# 19_RAM_Memory_module.net
KiCad netlist of a schematic drawn in Altium Designer
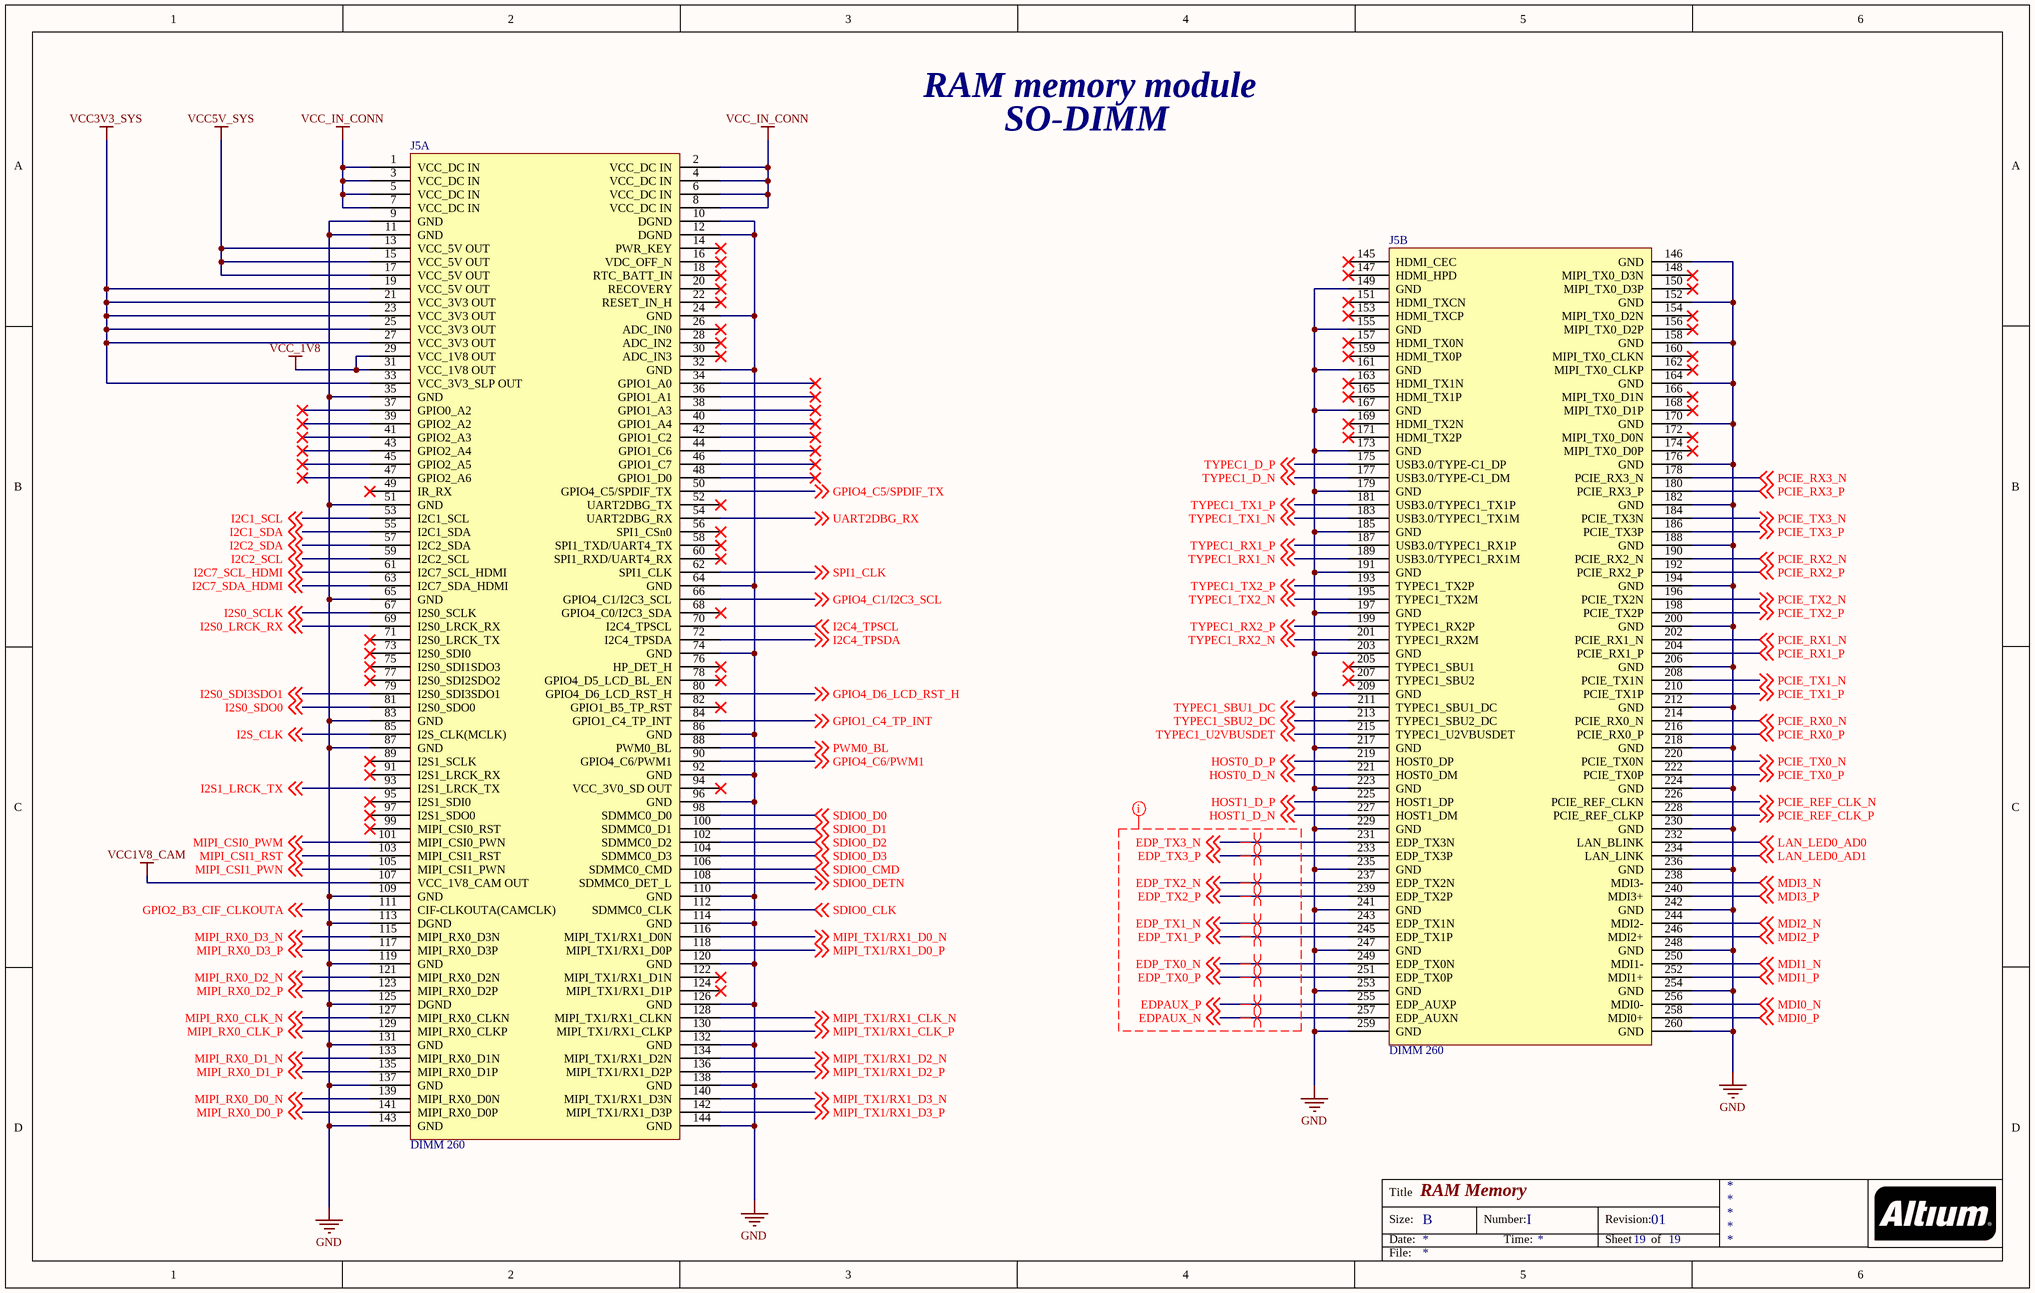
[diagram p0: [19] RAM Memory module.SchDoc]

(export (version "E")
  (design (tool "Eeschema 10.0.6"))
  (components
    (comp (ref "J5")
      (value "DIMM 260")
      (footprint "DIMM260_DDR4")
      (description "Dimm 260 pin smd plating on pcb")
      (fields (field (name "MANUFACTURER") "NA"))
      (libsource (lib "EsteemPCB_SOM_Course_intlib") (part "CON-DIMM_260-SMD"))
    )
  )
  (nets
    (net (code "1") (name "EDPAUX_N") (class "Default")
      (node (ref "J5") (pin "257") (pinfunction "EDP_AUXN_257") (pintype "passive"))
    )
    (net (code "2") (name "EDPAUX_P") (class "Default")
      (node (ref "J5") (pin "255") (pinfunction "EDP_AUXP_255") (pintype "passive"))
    )
    (net (code "3") (name "EDP_TX0_N") (class "Default")
      (node (ref "J5") (pin "249") (pinfunction "EDP_TX0N_249") (pintype "passive"))
    )
    (net (code "4") (name "EDP_TX0_P") (class "Default")
      (node (ref "J5") (pin "251") (pinfunction "EDP_TX0P_251") (pintype "passive"))
    )
    (net (code "5") (name "EDP_TX1_N") (class "Default")
      (node (ref "J5") (pin "243") (pinfunction "EDP_TX1N_243") (pintype "passive"))
    )
    (net (code "6") (name "EDP_TX1_P") (class "Default")
      (node (ref "J5") (pin "245") (pinfunction "EDP_TX1P_245") (pintype "passive"))
    )
    (net (code "7") (name "EDP_TX2_N") (class "Default")
      (node (ref "J5") (pin "237") (pinfunction "EDP_TX2N_237") (pintype "passive"))
    )
    (net (code "8") (name "EDP_TX2_P") (class "Default")
      (node (ref "J5") (pin "239") (pinfunction "EDP_TX2P_239") (pintype "passive"))
    )
    (net (code "9") (name "EDP_TX3_N") (class "Default")
      (node (ref "J5") (pin "231") (pinfunction "EDP_TX3N_231") (pintype "passive"))
    )
    (net (code "10") (name "EDP_TX3_P") (class "Default")
      (node (ref "J5") (pin "233") (pinfunction "EDP_TX3P_233") (pintype "passive"))
    )
    (net (code "11") (name "GND") (class "Default")
      (node (ref "J5") (pin "10") (pinfunction "DGND_10") (pintype "passive"))
      (node (ref "J5") (pin "109") (pinfunction "GND_109") (pintype "passive"))
      (node (ref "J5") (pin "11") (pinfunction "GND_11") (pintype "passive"))
      (node (ref "J5") (pin "110") (pinfunction "GND_110") (pintype "passive"))
      (node (ref "J5") (pin "113") (pinfunction "DGND_113") (pintype "passive"))
      (node (ref "J5") (pin "114") (pinfunction "GND_114") (pintype "passive"))
      (node (ref "J5") (pin "119") (pinfunction "GND_119") (pintype "passive"))
      (node (ref "J5") (pin "12") (pinfunction "DGND_12") (pintype "passive"))
      (node (ref "J5") (pin "120") (pinfunction "GND_120") (pintype "passive"))
      (node (ref "J5") (pin "125") (pinfunction "DGND_125") (pintype "passive"))
      (node (ref "J5") (pin "126") (pinfunction "GND_126") (pintype "passive"))
      (node (ref "J5") (pin "131") (pinfunction "GND_131") (pintype "passive"))
      (node (ref "J5") (pin "132") (pinfunction "GND_132") (pintype "passive"))
      (node (ref "J5") (pin "137") (pinfunction "GND_137") (pintype "passive"))
      (node (ref "J5") (pin "138") (pinfunction "GND_138") (pintype "passive"))
      (node (ref "J5") (pin "143") (pinfunction "GND_143") (pintype "passive"))
      (node (ref "J5") (pin "144") (pinfunction "GND_144") (pintype "passive"))
      (node (ref "J5") (pin "146") (pinfunction "GND_146") (pintype "passive"))
      (node (ref "J5") (pin "149") (pinfunction "GND_149") (pintype "passive"))
      (node (ref "J5") (pin "152") (pinfunction "GND_152") (pintype "passive"))
      (node (ref "J5") (pin "155") (pinfunction "GND_155") (pintype "passive"))
      (node (ref "J5") (pin "158") (pinfunction "GND_158") (pintype "passive"))
      (node (ref "J5") (pin "161") (pinfunction "GND_161") (pintype "passive"))
      (node (ref "J5") (pin "164") (pinfunction "GND_164") (pintype "passive"))
      (node (ref "J5") (pin "167") (pinfunction "GND_167") (pintype "passive"))
      (node (ref "J5") (pin "170") (pinfunction "GND_170") (pintype "passive"))
      (node (ref "J5") (pin "173") (pinfunction "GND_173") (pintype "passive"))
      (node (ref "J5") (pin "176") (pinfunction "GND_176") (pintype "passive"))
      (node (ref "J5") (pin "179") (pinfunction "GND_179") (pintype "passive"))
      (node (ref "J5") (pin "182") (pinfunction "GND_182") (pintype "passive"))
      (node (ref "J5") (pin "185") (pinfunction "GND_185") (pintype "passive"))
      (node (ref "J5") (pin "188") (pinfunction "GND_188") (pintype "passive"))
      (node (ref "J5") (pin "191") (pinfunction "GND_191") (pintype "passive"))
      (node (ref "J5") (pin "194") (pinfunction "GND_194") (pintype "passive"))
      (node (ref "J5") (pin "197") (pinfunction "GND_197") (pintype "passive"))
      (node (ref "J5") (pin "200") (pinfunction "GND_200") (pintype "passive"))
      (node (ref "J5") (pin "203") (pinfunction "GND_203") (pintype "passive"))
      (node (ref "J5") (pin "206") (pinfunction "GND_206") (pintype "passive"))
      (node (ref "J5") (pin "209") (pinfunction "GND_209") (pintype "passive"))
      (node (ref "J5") (pin "212") (pinfunction "GND_212") (pintype "passive"))
      (node (ref "J5") (pin "217") (pinfunction "GND_217") (pintype "passive"))
      (node (ref "J5") (pin "218") (pinfunction "GND_218") (pintype "passive"))
      (node (ref "J5") (pin "223") (pinfunction "GND_223") (pintype "passive"))
      (node (ref "J5") (pin "224") (pinfunction "GND_224") (pintype "passive"))
      (node (ref "J5") (pin "229") (pinfunction "GND_229") (pintype "passive"))
      (node (ref "J5") (pin "230") (pinfunction "GND_230") (pintype "passive"))
      (node (ref "J5") (pin "235") (pinfunction "GND_235") (pintype "passive"))
      (node (ref "J5") (pin "236") (pinfunction "GND_236") (pintype "passive"))
      (node (ref "J5") (pin "24") (pinfunction "GND_24") (pintype "passive"))
      (node (ref "J5") (pin "241") (pinfunction "GND_241") (pintype "passive"))
      (node (ref "J5") (pin "242") (pinfunction "GND_242") (pintype "passive"))
      (node (ref "J5") (pin "247") (pinfunction "GND_247") (pintype "passive"))
      (node (ref "J5") (pin "248") (pinfunction "GND_248") (pintype "passive"))
      (node (ref "J5") (pin "253") (pinfunction "GND_253") (pintype "passive"))
      (node (ref "J5") (pin "254") (pinfunction "GND_254") (pintype "passive"))
      (node (ref "J5") (pin "259") (pinfunction "GND_259") (pintype "passive"))
      (node (ref "J5") (pin "260") (pinfunction "GND_260") (pintype "passive"))
      (node (ref "J5") (pin "32") (pinfunction "GND_32") (pintype "passive"))
      (node (ref "J5") (pin "35") (pinfunction "GND_35") (pintype "passive"))
      (node (ref "J5") (pin "51") (pinfunction "GND_51") (pintype "passive"))
      (node (ref "J5") (pin "64") (pinfunction "GND_64") (pintype "passive"))
      (node (ref "J5") (pin "65") (pinfunction "GND_65") (pintype "passive"))
      (node (ref "J5") (pin "74") (pinfunction "GND_74") (pintype "passive"))
      (node (ref "J5") (pin "83") (pinfunction "GND_83") (pintype "passive"))
      (node (ref "J5") (pin "86") (pinfunction "GND_86") (pintype "passive"))
      (node (ref "J5") (pin "87") (pinfunction "GND_87") (pintype "passive"))
      (node (ref "J5") (pin "9") (pinfunction "GND_9") (pintype "passive"))
      (node (ref "J5") (pin "92") (pinfunction "GND_92") (pintype "passive"))
      (node (ref "J5") (pin "96") (pinfunction "GND_96") (pintype "passive"))
    )
    (net (code "12") (name "GPIO1_C4_TP_INT") (class "Default")
      (node (ref "J5") (pin "84") (pinfunction "GPIO1_C4_TP_INT_84") (pintype "passive"))
    )
    (net (code "13") (name "GPIO2_B3_CIF_CLKOUTA") (class "Default")
      (node (ref "J5") (pin "111") (pinfunction "CIF-CLKOUTA(CAMCLK)_111") (pintype "passive"))
    )
    (net (code "14") (name "GPIO4_C1{slash}I2C3_SCL") (class "Default")
      (node (ref "J5") (pin "66") (pinfunction "GPIO4_C1/I2C3_SCL_66") (pintype "passive"))
    )
    (net (code "15") (name "GPIO4_C5{slash}SPDIF_TX") (class "Default")
      (node (ref "J5") (pin "50") (pinfunction "GPIO4_C5/SPDIF_TX_50") (pintype "passive"))
    )
    (net (code "16") (name "GPIO4_C6{slash}PWM1") (class "Default")
      (node (ref "J5") (pin "90") (pinfunction "GPIO4_C6/PWM1_90") (pintype "passive"))
    )
    (net (code "17") (name "GPIO4_D6_LCD_RST_H") (class "Default")
      (node (ref "J5") (pin "80") (pinfunction "GPIO4_D6_LCD_RST_H_80") (pintype "passive"))
    )
    (net (code "18") (name "HOST0_D_N") (class "Default")
      (node (ref "J5") (pin "221") (pinfunction "HOST0_DM_221") (pintype "passive"))
    )
    (net (code "19") (name "HOST0_D_P") (class "Default")
      (node (ref "J5") (pin "219") (pinfunction "HOST0_DP_219") (pintype "passive"))
    )
    (net (code "20") (name "HOST1_D_N") (class "Default")
      (node (ref "J5") (pin "227") (pinfunction "HOST1_DM_227") (pintype "passive"))
    )
    (net (code "21") (name "HOST1_D_P") (class "Default")
      (node (ref "J5") (pin "225") (pinfunction "HOST1_DP_225") (pintype "passive"))
    )
    (net (code "22") (name "I2C1_SCL") (class "Default")
      (node (ref "J5") (pin "53") (pinfunction "I2C1_SCL_53") (pintype "passive"))
    )
    (net (code "23") (name "I2C1_SDA") (class "Default")
      (node (ref "J5") (pin "55") (pinfunction "I2C1_SDA_55") (pintype "passive"))
    )
    (net (code "24") (name "I2C2_SCL") (class "Default")
      (node (ref "J5") (pin "59") (pinfunction "I2C2_SCL_59") (pintype "passive"))
    )
    (net (code "25") (name "I2C2_SDA") (class "Default")
      (node (ref "J5") (pin "57") (pinfunction "I2C2_SDA_57") (pintype "passive"))
    )
    (net (code "26") (name "I2C4_TPSCL") (class "Default")
      (node (ref "J5") (pin "70") (pinfunction "I2C4_TPSCL_70") (pintype "passive"))
    )
    (net (code "27") (name "I2C4_TPSDA") (class "Default")
      (node (ref "J5") (pin "72") (pinfunction "I2C4_TPSDA_72") (pintype "passive"))
    )
    (net (code "28") (name "I2C7_SCL_HDMI") (class "Default")
      (node (ref "J5") (pin "61") (pinfunction "I2C7_SCL_HDMI_61") (pintype "passive"))
    )
    (net (code "29") (name "I2C7_SDA_HDMI") (class "Default")
      (node (ref "J5") (pin "63") (pinfunction "I2C7_SDA_HDMI_63") (pintype "passive"))
    )
    (net (code "30") (name "I2S0_LRCK_RX") (class "Default")
      (node (ref "J5") (pin "69") (pinfunction "I2S0_LRCK_RX_69") (pintype "passive"))
    )
    (net (code "31") (name "I2S0_SCLK") (class "Default")
      (node (ref "J5") (pin "67") (pinfunction "I2S0_SCLK_67") (pintype "passive"))
    )
    (net (code "32") (name "I2S0_SDI3SDO1") (class "Default")
      (node (ref "J5") (pin "79") (pinfunction "I2S0_SDI3SDO1_79") (pintype "passive"))
    )
    (net (code "33") (name "I2S0_SDO0") (class "Default")
      (node (ref "J5") (pin "81") (pinfunction "I2S0_SDO0_81") (pintype "passive"))
    )
    (net (code "34") (name "I2S1_LRCK_TX") (class "Default")
      (node (ref "J5") (pin "93") (pinfunction "I2S1_LRCK_TX_93") (pintype "passive"))
    )
    (net (code "35") (name "I2S_CLK") (class "Default")
      (node (ref "J5") (pin "85") (pinfunction "I2S_CLK(MCLK)_85") (pintype "passive"))
    )
    (net (code "36") (name "LAN_LED0_AD0") (class "Default")
      (node (ref "J5") (pin "232") (pinfunction "LAN_BLINK_232") (pintype "passive"))
    )
    (net (code "37") (name "LAN_LED0_AD1") (class "Default")
      (node (ref "J5") (pin "234") (pinfunction "LAN_LINK_234") (pintype "passive"))
    )
    (net (code "38") (name "MDI0_N") (class "Default")
      (node (ref "J5") (pin "256") (pinfunction "MDI0-_256") (pintype "passive"))
    )
    (net (code "39") (name "MDI0_P") (class "Default")
      (node (ref "J5") (pin "258") (pinfunction "MDI0+_258") (pintype "passive"))
    )
    (net (code "40") (name "MDI1_N") (class "Default")
      (node (ref "J5") (pin "250") (pinfunction "MDI1-_250") (pintype "passive"))
    )
    (net (code "41") (name "MDI1_P") (class "Default")
      (node (ref "J5") (pin "252") (pinfunction "MDI1+_252") (pintype "passive"))
    )
    (net (code "42") (name "MDI2_N") (class "Default")
      (node (ref "J5") (pin "244") (pinfunction "MDI2-_244") (pintype "passive"))
    )
    (net (code "43") (name "MDI2_P") (class "Default")
      (node (ref "J5") (pin "246") (pinfunction "MDI2+_246") (pintype "passive"))
    )
    (net (code "44") (name "MDI3_N") (class "Default")
      (node (ref "J5") (pin "238") (pinfunction "MDI3-_238") (pintype "passive"))
    )
    (net (code "45") (name "MDI3_P") (class "Default")
      (node (ref "J5") (pin "240") (pinfunction "MDI3+_240") (pintype "passive"))
    )
    (net (code "46") (name "MIPI_CSI0_PWM") (class "Default")
      (node (ref "J5") (pin "101") (pinfunction "MIPI_CSI0_PWN_101") (pintype "passive"))
    )
    (net (code "47") (name "MIPI_CSI1_PWN") (class "Default")
      (node (ref "J5") (pin "105") (pinfunction "MIPI_CSI1_PWN_105") (pintype "passive"))
    )
    (net (code "48") (name "MIPI_CSI1_RST") (class "Default")
      (node (ref "J5") (pin "103") (pinfunction "MIPI_CSI1_RST_103") (pintype "passive"))
    )
    (net (code "49") (name "MIPI_RX0_CLK_N") (class "Default")
      (node (ref "J5") (pin "127") (pinfunction "MIPI_RX0_CLKN_127") (pintype "passive"))
    )
    (net (code "50") (name "MIPI_RX0_CLK_P") (class "Default")
      (node (ref "J5") (pin "129") (pinfunction "MIPI_RX0_CLKP_129") (pintype "passive"))
    )
    (net (code "51") (name "MIPI_RX0_D0_N") (class "Default")
      (node (ref "J5") (pin "139") (pinfunction "MIPI_RX0_D0N_139") (pintype "passive"))
    )
    (net (code "52") (name "MIPI_RX0_D0_P") (class "Default")
      (node (ref "J5") (pin "141") (pinfunction "MIPI_RX0_D0P_141") (pintype "passive"))
    )
    (net (code "53") (name "MIPI_RX0_D1_N") (class "Default")
      (node (ref "J5") (pin "133") (pinfunction "MIPI_RX0_D1N_133") (pintype "passive"))
    )
    (net (code "54") (name "MIPI_RX0_D1_P") (class "Default")
      (node (ref "J5") (pin "135") (pinfunction "MIPI_RX0_D1P_135") (pintype "passive"))
    )
    (net (code "55") (name "MIPI_RX0_D2_N") (class "Default")
      (node (ref "J5") (pin "121") (pinfunction "MIPI_RX0_D2N_121") (pintype "passive"))
    )
    (net (code "56") (name "MIPI_RX0_D2_P") (class "Default")
      (node (ref "J5") (pin "123") (pinfunction "MIPI_RX0_D2P_123") (pintype "passive"))
    )
    (net (code "57") (name "MIPI_RX0_D3_N") (class "Default")
      (node (ref "J5") (pin "115") (pinfunction "MIPI_RX0_D3N_115") (pintype "passive"))
    )
    (net (code "58") (name "MIPI_RX0_D3_P") (class "Default")
      (node (ref "J5") (pin "117") (pinfunction "MIPI_RX0_D3P_117") (pintype "passive"))
    )
    (net (code "59") (name "MIPI_TX1{slash}RX1_CLK_N") (class "Default")
      (node (ref "J5") (pin "128") (pinfunction "MIPI_TX1/RX1_CLKN_128") (pintype "passive"))
    )
    (net (code "60") (name "MIPI_TX1{slash}RX1_CLK_P") (class "Default")
      (node (ref "J5") (pin "130") (pinfunction "MIPI_TX1/RX1_CLKP_130") (pintype "passive"))
    )
    (net (code "61") (name "MIPI_TX1{slash}RX1_D0_N") (class "Default")
      (node (ref "J5") (pin "116") (pinfunction "MIPI_TX1/RX1_D0N_116") (pintype "passive"))
    )
    (net (code "62") (name "MIPI_TX1{slash}RX1_D0_P") (class "Default")
      (node (ref "J5") (pin "118") (pinfunction "MIPI_TX1/RX1_D0P_118") (pintype "passive"))
    )
    (net (code "63") (name "MIPI_TX1{slash}RX1_D2_N") (class "Default")
      (node (ref "J5") (pin "134") (pinfunction "MIPI_TX1/RX1_D2N_134") (pintype "passive"))
    )
    (net (code "64") (name "MIPI_TX1{slash}RX1_D2_P") (class "Default")
      (node (ref "J5") (pin "136") (pinfunction "MIPI_TX1/RX1_D2P_136") (pintype "passive"))
    )
    (net (code "65") (name "MIPI_TX1{slash}RX1_D3_N") (class "Default")
      (node (ref "J5") (pin "140") (pinfunction "MIPI_TX1/RX1_D3N_140") (pintype "passive"))
    )
    (net (code "66") (name "MIPI_TX1{slash}RX1_D3_P") (class "Default")
      (node (ref "J5") (pin "142") (pinfunction "MIPI_TX1/RX1_D3P_142") (pintype "passive"))
    )
    (net (code "67") (name "PCIE_REF_CLK_N") (class "Default")
      (node (ref "J5") (pin "226") (pinfunction "PCIE_REF_CLKN_226") (pintype "passive"))
    )
    (net (code "68") (name "PCIE_REF_CLK_P") (class "Default")
      (node (ref "J5") (pin "228") (pinfunction "PCIE_REF_CLKP_228") (pintype "passive"))
    )
    (net (code "69") (name "PCIE_RX0_N") (class "Default")
      (node (ref "J5") (pin "214") (pinfunction "PCIE_RX0_N_214") (pintype "passive"))
    )
    (net (code "70") (name "PCIE_RX0_P") (class "Default")
      (node (ref "J5") (pin "216") (pinfunction "PCIE_RX0_P_216") (pintype "passive"))
    )
    (net (code "71") (name "PCIE_RX1_N") (class "Default")
      (node (ref "J5") (pin "202") (pinfunction "PCIE_RX1_N_202") (pintype "passive"))
    )
    (net (code "72") (name "PCIE_RX1_P") (class "Default")
      (node (ref "J5") (pin "204") (pinfunction "PCIE_RX1_P_204") (pintype "passive"))
    )
    (net (code "73") (name "PCIE_RX2_N") (class "Default")
      (node (ref "J5") (pin "190") (pinfunction "PCIE_RX2_N_190") (pintype "passive"))
    )
    (net (code "74") (name "PCIE_RX2_P") (class "Default")
      (node (ref "J5") (pin "192") (pinfunction "PCIE_RX2_P_192") (pintype "passive"))
    )
    (net (code "75") (name "PCIE_RX3_N") (class "Default")
      (node (ref "J5") (pin "178") (pinfunction "PCIE_RX3_N_178") (pintype "passive"))
    )
    (net (code "76") (name "PCIE_RX3_P") (class "Default")
      (node (ref "J5") (pin "180") (pinfunction "PCIE_RX3_P_180") (pintype "passive"))
    )
    (net (code "77") (name "PCIE_TX0_N") (class "Default")
      (node (ref "J5") (pin "220") (pinfunction "PCIE_TX0N_220") (pintype "passive"))
    )
    (net (code "78") (name "PCIE_TX0_P") (class "Default")
      (node (ref "J5") (pin "222") (pinfunction "PCIE_TX0P_222") (pintype "passive"))
    )
    (net (code "79") (name "PCIE_TX1_N") (class "Default")
      (node (ref "J5") (pin "208") (pinfunction "PCIE_TX1N_208") (pintype "passive"))
    )
    (net (code "80") (name "PCIE_TX1_P") (class "Default")
      (node (ref "J5") (pin "210") (pinfunction "PCIE_TX1P_210") (pintype "passive"))
    )
    (net (code "81") (name "PCIE_TX2_N") (class "Default")
      (node (ref "J5") (pin "196") (pinfunction "PCIE_TX2N_196") (pintype "passive"))
    )
    (net (code "82") (name "PCIE_TX2_P") (class "Default")
      (node (ref "J5") (pin "198") (pinfunction "PCIE_TX2P_198") (pintype "passive"))
    )
    (net (code "83") (name "PCIE_TX3_N") (class "Default")
      (node (ref "J5") (pin "184") (pinfunction "PCIE_TX3N_184") (pintype "passive"))
    )
    (net (code "84") (name "PCIE_TX3_P") (class "Default")
      (node (ref "J5") (pin "186") (pinfunction "PCIE_TX3P_186") (pintype "passive"))
    )
    (net (code "85") (name "PWM0_BL") (class "Default")
      (node (ref "J5") (pin "88") (pinfunction "PWM0_BL_88") (pintype "passive"))
    )
    (net (code "86") (name "SDIO0_CLK") (class "Default")
      (node (ref "J5") (pin "112") (pinfunction "SDMMC0_CLK_112") (pintype "passive"))
    )
    (net (code "87") (name "SDIO0_CMD") (class "Default")
      (node (ref "J5") (pin "106") (pinfunction "SDMMC0_CMD_106") (pintype "passive"))
    )
    (net (code "88") (name "SDIO0_D0") (class "Default")
      (node (ref "J5") (pin "98") (pinfunction "SDMMC0_D0_98") (pintype "passive"))
    )
    (net (code "89") (name "SDIO0_D1") (class "Default")
      (node (ref "J5") (pin "100") (pinfunction "SDMMC0_D1_100") (pintype "passive"))
    )
    (net (code "90") (name "SDIO0_D2") (class "Default")
      (node (ref "J5") (pin "102") (pinfunction "SDMMC0_D2_102") (pintype "passive"))
    )
    (net (code "91") (name "SDIO0_D3") (class "Default")
      (node (ref "J5") (pin "104") (pinfunction "SDMMC0_D3_104") (pintype "passive"))
    )
    (net (code "92") (name "SDIO0_DETN") (class "Default")
      (node (ref "J5") (pin "108") (pinfunction "SDMMC0_DET_L_108") (pintype "passive"))
    )
    (net (code "93") (name "SPI1_CLK") (class "Default")
      (node (ref "J5") (pin "62") (pinfunction "SPI1_CLK_62") (pintype "passive"))
    )
    (net (code "94") (name "TYPEC1_D_N") (class "Default")
      (node (ref "J5") (pin "177") (pinfunction "USB3.0/TYPE-C1_DM_177") (pintype "passive"))
    )
    (net (code "95") (name "TYPEC1_D_P") (class "Default")
      (node (ref "J5") (pin "175") (pinfunction "USB3.0/TYPE-C1_DP_175") (pintype "passive"))
    )
    (net (code "96") (name "TYPEC1_RX1_N") (class "Default")
      (node (ref "J5") (pin "189") (pinfunction "USB3.0/TYPEC1_RX1M_189") (pintype "passive"))
    )
    (net (code "97") (name "TYPEC1_RX1_P") (class "Default")
      (node (ref "J5") (pin "187") (pinfunction "USB3.0/TYPEC1_RX1P_187") (pintype "passive"))
    )
    (net (code "98") (name "TYPEC1_RX2_N") (class "Default")
      (node (ref "J5") (pin "201") (pinfunction "TYPEC1_RX2M_201") (pintype "passive"))
    )
    (net (code "99") (name "TYPEC1_RX2_P") (class "Default")
      (node (ref "J5") (pin "199") (pinfunction "TYPEC1_RX2P_199") (pintype "passive"))
    )
    (net (code "100") (name "TYPEC1_SBU1_DC") (class "Default")
      (node (ref "J5") (pin "211") (pinfunction "TYPEC1_SBU1_DC_211") (pintype "passive"))
    )
    (net (code "101") (name "TYPEC1_SBU2_DC") (class "Default")
      (node (ref "J5") (pin "213") (pinfunction "TYPEC1_SBU2_DC_213") (pintype "passive"))
    )
    (net (code "102") (name "TYPEC1_TX1_N") (class "Default")
      (node (ref "J5") (pin "183") (pinfunction "USB3.0/TYPEC1_TX1M_183") (pintype "passive"))
    )
    (net (code "103") (name "TYPEC1_TX1_P") (class "Default")
      (node (ref "J5") (pin "181") (pinfunction "USB3.0/TYPEC1_TX1P_181") (pintype "passive"))
    )
    (net (code "104") (name "TYPEC1_TX2_N") (class "Default")
      (node (ref "J5") (pin "195") (pinfunction "TYPEC1_TX2M_195") (pintype "passive"))
    )
    (net (code "105") (name "TYPEC1_TX2_P") (class "Default")
      (node (ref "J5") (pin "193") (pinfunction "TYPEC1_TX2P_193") (pintype "passive"))
    )
    (net (code "106") (name "TYPEC1_U2VBUSDET") (class "Default")
      (node (ref "J5") (pin "215") (pinfunction "TYPEC1_U2VBUSDET_215") (pintype "passive"))
    )
    (net (code "107") (name "UART2DBG_RX") (class "Default")
      (node (ref "J5") (pin "54") (pinfunction "UART2DBG_RX_54") (pintype "passive"))
    )
    (net (code "108") (name "VCC1V8_CAM") (class "Default")
      (node (ref "J5") (pin "107") (pinfunction "VCC_1V8_CAM_OUT_107") (pintype "passive"))
    )
    (net (code "109") (name "VCC3V3_SYS") (class "Default")
      (node (ref "J5") (pin "19") (pinfunction "VCC_5V_OUT_19") (pintype "passive"))
      (node (ref "J5") (pin "21") (pinfunction "VCC_3V3_OUT_21") (pintype "passive"))
      (node (ref "J5") (pin "23") (pinfunction "VCC_3V3_OUT_23") (pintype "passive"))
      (node (ref "J5") (pin "25") (pinfunction "VCC_3V3_OUT_25") (pintype "passive"))
      (node (ref "J5") (pin "27") (pinfunction "VCC_3V3_OUT_27") (pintype "passive"))
      (node (ref "J5") (pin "33") (pinfunction "VCC_3V3_SLP_OUT_33") (pintype "passive"))
    )
    (net (code "110") (name "VCC5V_SYS") (class "Default")
      (node (ref "J5") (pin "13") (pinfunction "VCC_5V_OUT_13") (pintype "passive"))
      (node (ref "J5") (pin "15") (pinfunction "VCC_5V_OUT_15") (pintype "passive"))
      (node (ref "J5") (pin "17") (pinfunction "VCC_5V_OUT_17") (pintype "passive"))
    )
    (net (code "111") (name "VCC_1V8") (class "Default")
      (node (ref "J5") (pin "29") (pinfunction "VCC_1V8_OUT_29") (pintype "passive"))
      (node (ref "J5") (pin "31") (pinfunction "VCC_1V8_OUT_31") (pintype "passive"))
    )
    (net (code "112") (name "VCC_IN_CONN") (class "Default")
      (node (ref "J5") (pin "1") (pinfunction "VCC_DC_IN_1") (pintype "passive"))
      (node (ref "J5") (pin "2") (pinfunction "VCC_DC_IN_2") (pintype "passive"))
      (node (ref "J5") (pin "3") (pinfunction "VCC_DC_IN_3") (pintype "passive"))
      (node (ref "J5") (pin "4") (pinfunction "VCC_DC_IN_4") (pintype "passive"))
      (node (ref "J5") (pin "5") (pinfunction "VCC_DC_IN_5") (pintype "passive"))
      (node (ref "J5") (pin "6") (pinfunction "VCC_DC_IN_6") (pintype "passive"))
      (node (ref "J5") (pin "7") (pinfunction "VCC_DC_IN_7") (pintype "passive"))
      (node (ref "J5") (pin "8") (pinfunction "VCC_DC_IN_8") (pintype "passive"))
    )
    (net (code "113") (name "unconnected-(J5A-ADC_IN0-Pad26)") (class "Default")
      (node (ref "J5") (pin "26") (pinfunction "ADC_IN0_26") (pintype "passive+no_connect"))
    )
    (net (code "114") (name "unconnected-(J5A-ADC_IN2-Pad28)") (class "Default")
      (node (ref "J5") (pin "28") (pinfunction "ADC_IN2_28") (pintype "passive+no_connect"))
    )
    (net (code "115") (name "unconnected-(J5A-ADC_IN3-Pad30)") (class "Default")
      (node (ref "J5") (pin "30") (pinfunction "ADC_IN3_30") (pintype "passive+no_connect"))
    )
    (net (code "116") (name "unconnected-(J5A-GPIO0_A2-Pad37)") (class "Default")
      (node (ref "J5") (pin "37") (pinfunction "GPIO0_A2_37") (pintype "passive+no_connect"))
    )
    (net (code "117") (name "unconnected-(J5A-GPIO1_A0-Pad34)") (class "Default")
      (node (ref "J5") (pin "34") (pinfunction "GPIO1_A0_34") (pintype "passive+no_connect"))
    )
    (net (code "118") (name "unconnected-(J5A-GPIO1_A1-Pad36)") (class "Default")
      (node (ref "J5") (pin "36") (pinfunction "GPIO1_A1_36") (pintype "passive+no_connect"))
    )
    (net (code "119") (name "unconnected-(J5A-GPIO1_A3-Pad38)") (class "Default")
      (node (ref "J5") (pin "38") (pinfunction "GPIO1_A3_38") (pintype "passive+no_connect"))
    )
    (net (code "120") (name "unconnected-(J5A-GPIO1_A4-Pad40)") (class "Default")
      (node (ref "J5") (pin "40") (pinfunction "GPIO1_A4_40") (pintype "passive+no_connect"))
    )
    (net (code "121") (name "unconnected-(J5A-GPIO1_B5_TP_RST-Pad82)") (class "Default")
      (node (ref "J5") (pin "82") (pinfunction "GPIO1_B5_TP_RST_82") (pintype "passive+no_connect"))
    )
    (net (code "122") (name "unconnected-(J5A-GPIO1_C2-Pad42)") (class "Default")
      (node (ref "J5") (pin "42") (pinfunction "GPIO1_C2_42") (pintype "passive+no_connect"))
    )
    (net (code "123") (name "unconnected-(J5A-GPIO1_C6-Pad44)") (class "Default")
      (node (ref "J5") (pin "44") (pinfunction "GPIO1_C6_44") (pintype "passive+no_connect"))
    )
    (net (code "124") (name "unconnected-(J5A-GPIO1_C7-Pad46)") (class "Default")
      (node (ref "J5") (pin "46") (pinfunction "GPIO1_C7_46") (pintype "passive+no_connect"))
    )
    (net (code "125") (name "unconnected-(J5A-GPIO1_D0-Pad48)") (class "Default")
      (node (ref "J5") (pin "48") (pinfunction "GPIO1_D0_48") (pintype "passive+no_connect"))
    )
    (net (code "126") (name "unconnected-(J5A-GPIO2_A2-Pad39)") (class "Default")
      (node (ref "J5") (pin "39") (pinfunction "GPIO2_A2_39") (pintype "passive+no_connect"))
    )
    (net (code "127") (name "unconnected-(J5A-GPIO2_A3-Pad41)") (class "Default")
      (node (ref "J5") (pin "41") (pinfunction "GPIO2_A3_41") (pintype "passive+no_connect"))
    )
    (net (code "128") (name "unconnected-(J5A-GPIO2_A4-Pad43)") (class "Default")
      (node (ref "J5") (pin "43") (pinfunction "GPIO2_A4_43") (pintype "passive+no_connect"))
    )
    (net (code "129") (name "unconnected-(J5A-GPIO2_A5-Pad45)") (class "Default")
      (node (ref "J5") (pin "45") (pinfunction "GPIO2_A5_45") (pintype "passive+no_connect"))
    )
    (net (code "130") (name "unconnected-(J5A-GPIO2_A6-Pad47)") (class "Default")
      (node (ref "J5") (pin "47") (pinfunction "GPIO2_A6_47") (pintype "passive+no_connect"))
    )
    (net (code "131") (name "unconnected-(J5A-GPIO4_C0{slash}I2C3_SDA-Pad68)") (class "Default")
      (node (ref "J5") (pin "68") (pinfunction "GPIO4_C0/I2C3_SDA_68") (pintype "passive+no_connect"))
    )
    (net (code "132") (name "unconnected-(J5A-GPIO4_D5_LCD_BL_EN-Pad78)") (class "Default")
      (node (ref "J5") (pin "78") (pinfunction "GPIO4_D5_LCD_BL_EN_78") (pintype "passive+no_connect"))
    )
    (net (code "133") (name "unconnected-(J5A-HP_DET_H-Pad76)") (class "Default")
      (node (ref "J5") (pin "76") (pinfunction "HP_DET_H_76") (pintype "passive+no_connect"))
    )
    (net (code "134") (name "unconnected-(J5A-I2S0_LRCK_TX-Pad71)") (class "Default")
      (node (ref "J5") (pin "71") (pinfunction "I2S0_LRCK_TX_71") (pintype "passive+no_connect"))
    )
    (net (code "135") (name "unconnected-(J5A-I2S0_SDI0-Pad73)") (class "Default")
      (node (ref "J5") (pin "73") (pinfunction "I2S0_SDI0_73") (pintype "passive+no_connect"))
    )
    (net (code "136") (name "unconnected-(J5A-I2S0_SDI1SDO3-Pad75)") (class "Default")
      (node (ref "J5") (pin "75") (pinfunction "I2S0_SDI1SDO3_75") (pintype "passive+no_connect"))
    )
    (net (code "137") (name "unconnected-(J5A-I2S0_SDI2SDO2-Pad77)") (class "Default")
      (node (ref "J5") (pin "77") (pinfunction "I2S0_SDI2SDO2_77") (pintype "passive+no_connect"))
    )
    (net (code "138") (name "unconnected-(J5A-I2S1_LRCK_RX-Pad91)") (class "Default")
      (node (ref "J5") (pin "91") (pinfunction "I2S1_LRCK_RX_91") (pintype "passive+no_connect"))
    )
    (net (code "139") (name "unconnected-(J5A-I2S1_SCLK-Pad89)") (class "Default")
      (node (ref "J5") (pin "89") (pinfunction "I2S1_SCLK_89") (pintype "passive+no_connect"))
    )
    (net (code "140") (name "unconnected-(J5A-I2S1_SDI0-Pad95)") (class "Default")
      (node (ref "J5") (pin "95") (pinfunction "I2S1_SDI0_95") (pintype "passive+no_connect"))
    )
    (net (code "141") (name "unconnected-(J5A-I2S1_SDO0-Pad97)") (class "Default")
      (node (ref "J5") (pin "97") (pinfunction "I2S1_SDO0_97") (pintype "passive+no_connect"))
    )
    (net (code "142") (name "unconnected-(J5A-IR_RX-Pad49)") (class "Default")
      (node (ref "J5") (pin "49") (pinfunction "IR_RX_49") (pintype "passive+no_connect"))
    )
    (net (code "143") (name "unconnected-(J5A-MIPI_CSI0_RST-Pad99)") (class "Default")
      (node (ref "J5") (pin "99") (pinfunction "MIPI_CSI0_RST_99") (pintype "passive+no_connect"))
    )
    (net (code "144") (name "unconnected-(J5A-MIPI_TX1{slash}RX1_D1N-Pad122)") (class "Default")
      (node (ref "J5") (pin "122") (pinfunction "MIPI_TX1/RX1_D1N_122") (pintype "passive+no_connect"))
    )
    (net (code "145") (name "unconnected-(J5A-MIPI_TX1{slash}RX1_D1P-Pad124)") (class "Default")
      (node (ref "J5") (pin "124") (pinfunction "MIPI_TX1/RX1_D1P_124") (pintype "passive+no_connect"))
    )
    (net (code "146") (name "unconnected-(J5A-PWR_KEY-Pad14)") (class "Default")
      (node (ref "J5") (pin "14") (pinfunction "PWR_KEY_14") (pintype "passive+no_connect"))
    )
    (net (code "147") (name "unconnected-(J5A-RECOVERY-Pad20)") (class "Default")
      (node (ref "J5") (pin "20") (pinfunction "RECOVERY_20") (pintype "passive+no_connect"))
    )
    (net (code "148") (name "unconnected-(J5A-RESET_IN_H-Pad22)") (class "Default")
      (node (ref "J5") (pin "22") (pinfunction "RESET_IN_H_22") (pintype "passive+no_connect"))
    )
    (net (code "149") (name "unconnected-(J5A-RTC_BATT_IN-Pad18)") (class "Default")
      (node (ref "J5") (pin "18") (pinfunction "RTC_BATT_IN_18") (pintype "passive+no_connect"))
    )
    (net (code "150") (name "unconnected-(J5A-SPI1_CSn0-Pad56)") (class "Default")
      (node (ref "J5") (pin "56") (pinfunction "SPI1_CSn0_56") (pintype "passive+no_connect"))
    )
    (net (code "151") (name "unconnected-(J5A-SPI1_RXD{slash}UART4_RX-Pad60)") (class "Default")
      (node (ref "J5") (pin "60") (pinfunction "SPI1_RXD/UART4_RX_60") (pintype "passive+no_connect"))
    )
    (net (code "152") (name "unconnected-(J5A-SPI1_TXD{slash}UART4_TX-Pad58)") (class "Default")
      (node (ref "J5") (pin "58") (pinfunction "SPI1_TXD/UART4_TX_58") (pintype "passive+no_connect"))
    )
    (net (code "153") (name "unconnected-(J5A-UART2DBG_TX-Pad52)") (class "Default")
      (node (ref "J5") (pin "52") (pinfunction "UART2DBG_TX_52") (pintype "passive+no_connect"))
    )
    (net (code "154") (name "unconnected-(J5A-VCC_3V0_SD_OUT-Pad94)") (class "Default")
      (node (ref "J5") (pin "94") (pinfunction "VCC_3V0_SD_OUT_94") (pintype "passive+no_connect"))
    )
    (net (code "155") (name "unconnected-(J5A-VDC_OFF_N-Pad16)") (class "Default")
      (node (ref "J5") (pin "16") (pinfunction "VDC_OFF_N_16") (pintype "passive+no_connect"))
    )
    (net (code "156") (name "unconnected-(J5B-HDMI_CEC-Pad145)") (class "Default")
      (node (ref "J5") (pin "145") (pinfunction "HDMI_CEC_145") (pintype "passive+no_connect"))
    )
    (net (code "157") (name "unconnected-(J5B-HDMI_HPD-Pad147)") (class "Default")
      (node (ref "J5") (pin "147") (pinfunction "HDMI_HPD_147") (pintype "passive+no_connect"))
    )
    (net (code "158") (name "unconnected-(J5B-HDMI_TX0N-Pad157)") (class "Default")
      (node (ref "J5") (pin "157") (pinfunction "HDMI_TX0N_157") (pintype "passive+no_connect"))
    )
    (net (code "159") (name "unconnected-(J5B-HDMI_TX0P-Pad159)") (class "Default")
      (node (ref "J5") (pin "159") (pinfunction "HDMI_TX0P_159") (pintype "passive+no_connect"))
    )
    (net (code "160") (name "unconnected-(J5B-HDMI_TX1N-Pad163)") (class "Default")
      (node (ref "J5") (pin "163") (pinfunction "HDMI_TX1N_163") (pintype "passive+no_connect"))
    )
    (net (code "161") (name "unconnected-(J5B-HDMI_TX1P-Pad165)") (class "Default")
      (node (ref "J5") (pin "165") (pinfunction "HDMI_TX1P_165") (pintype "passive+no_connect"))
    )
    (net (code "162") (name "unconnected-(J5B-HDMI_TX2N-Pad169)") (class "Default")
      (node (ref "J5") (pin "169") (pinfunction "HDMI_TX2N_169") (pintype "passive+no_connect"))
    )
    (net (code "163") (name "unconnected-(J5B-HDMI_TX2P-Pad171)") (class "Default")
      (node (ref "J5") (pin "171") (pinfunction "HDMI_TX2P_171") (pintype "passive+no_connect"))
    )
    (net (code "164") (name "unconnected-(J5B-HDMI_TXCN-Pad151)") (class "Default")
      (node (ref "J5") (pin "151") (pinfunction "HDMI_TXCN_151") (pintype "passive+no_connect"))
    )
    (net (code "165") (name "unconnected-(J5B-HDMI_TXCP-Pad153)") (class "Default")
      (node (ref "J5") (pin "153") (pinfunction "HDMI_TXCP_153") (pintype "passive+no_connect"))
    )
    (net (code "166") (name "unconnected-(J5B-MIPI_TX0_CLKN-Pad160)") (class "Default")
      (node (ref "J5") (pin "160") (pinfunction "MIPI_TX0_CLKN_160") (pintype "passive+no_connect"))
    )
    (net (code "167") (name "unconnected-(J5B-MIPI_TX0_CLKP-Pad162)") (class "Default")
      (node (ref "J5") (pin "162") (pinfunction "MIPI_TX0_CLKP_162") (pintype "passive+no_connect"))
    )
    (net (code "168") (name "unconnected-(J5B-MIPI_TX0_D0N-Pad172)") (class "Default")
      (node (ref "J5") (pin "172") (pinfunction "MIPI_TX0_D0N_172") (pintype "passive+no_connect"))
    )
    (net (code "169") (name "unconnected-(J5B-MIPI_TX0_D0P-Pad174)") (class "Default")
      (node (ref "J5") (pin "174") (pinfunction "MIPI_TX0_D0P_174") (pintype "passive+no_connect"))
    )
    (net (code "170") (name "unconnected-(J5B-MIPI_TX0_D1N-Pad166)") (class "Default")
      (node (ref "J5") (pin "166") (pinfunction "MIPI_TX0_D1N_166") (pintype "passive+no_connect"))
    )
    (net (code "171") (name "unconnected-(J5B-MIPI_TX0_D1P-Pad168)") (class "Default")
      (node (ref "J5") (pin "168") (pinfunction "MIPI_TX0_D1P_168") (pintype "passive+no_connect"))
    )
    (net (code "172") (name "unconnected-(J5B-MIPI_TX0_D2N-Pad154)") (class "Default")
      (node (ref "J5") (pin "154") (pinfunction "MIPI_TX0_D2N_154") (pintype "passive+no_connect"))
    )
    (net (code "173") (name "unconnected-(J5B-MIPI_TX0_D2P-Pad156)") (class "Default")
      (node (ref "J5") (pin "156") (pinfunction "MIPI_TX0_D2P_156") (pintype "passive+no_connect"))
    )
    (net (code "174") (name "unconnected-(J5B-MIPI_TX0_D3N-Pad148)") (class "Default")
      (node (ref "J5") (pin "148") (pinfunction "MIPI_TX0_D3N_148") (pintype "passive+no_connect"))
    )
    (net (code "175") (name "unconnected-(J5B-MIPI_TX0_D3P-Pad150)") (class "Default")
      (node (ref "J5") (pin "150") (pinfunction "MIPI_TX0_D3P_150") (pintype "passive+no_connect"))
    )
    (net (code "176") (name "unconnected-(J5B-TYPEC1_SBU1-Pad205)") (class "Default")
      (node (ref "J5") (pin "205") (pinfunction "TYPEC1_SBU1_205") (pintype "passive+no_connect"))
    )
    (net (code "177") (name "unconnected-(J5B-TYPEC1_SBU2-Pad207)") (class "Default")
      (node (ref "J5") (pin "207") (pinfunction "TYPEC1_SBU2_207") (pintype "passive+no_connect"))
    )
  )
)
